# Sheet2.net
KiCad netlist of a schematic drawn in Altium Designer
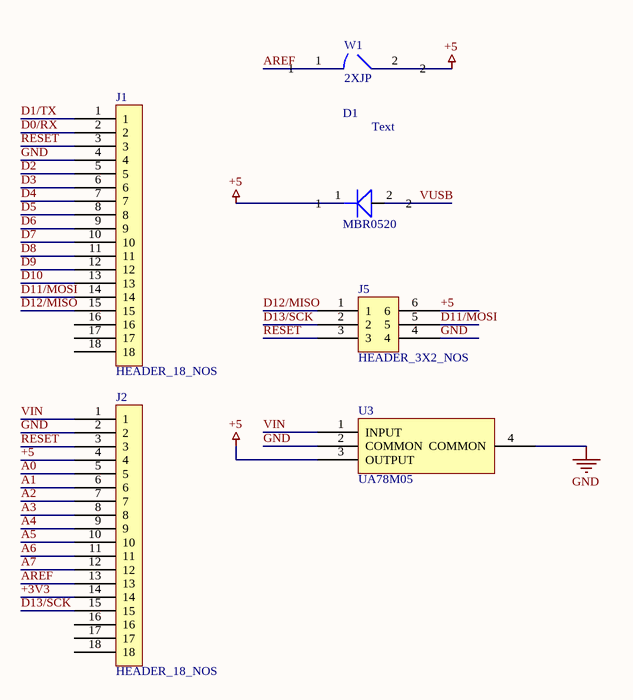
[diagram p0: Sheet2.SchDoc]

(export (version "E")
  (design (tool "Eeschema 10.0.6"))
  (components
    (comp (ref "D1")
      (value "MBR0520")
      (footprint "shotkey diode sod962")
      (libsource (lib "diode") (part "Component_1"))
    )
    (comp (ref "J1")
      (value "HEADER_18_NOS")
      (footprint "DIP18")
      (libsource (lib "18_x_1_header_pins") (part "Component_1"))
    )
    (comp (ref "J2")
      (value "HEADER_18_NOS")
      (footprint "DIP18")
      (libsource (lib "18_x_1_header_pins") (part "Component_1"))
    )
    (comp (ref "J5")
      (value "HEADER_3X2_NOS")
      (footprint "DIP6")
      (libsource (lib "3x2_header") (part "Component_1"))
    )
    (comp (ref "U3")
      (value "UA78M05")
      (footprint "SOT223-4")
      (libsource (lib "vol_reg") (part "Component_1"))
    )
    (comp (ref "W1") (value "2XJP") (footprint "switch") (libsource (lib "switch") (part "Component_1")))
  )
  (nets
    (net (code "1") (name "+5") (class "Default")
      (node (ref "D1") (pin "1") (pinfunction "1_1") (pintype "passive"))
      (node (ref "J2") (pin "4") (pinfunction "4_4") (pintype "passive"))
      (node (ref "J5") (pin "6") (pinfunction "6_6") (pintype "passive"))
      (node (ref "U3") (pin "3") (pinfunction "OUTPUT_3") (pintype "passive"))
      (node (ref "W1") (pin "2") (pinfunction "2_2") (pintype "passive"))
    )
    (net (code "2") (name "/+3V3") (class "Default")
      (node (ref "J2") (pin "14") (pinfunction "14_14") (pintype "passive"))
    )
    (net (code "3") (name "/A0") (class "Default")
      (node (ref "J2") (pin "5") (pinfunction "5_5") (pintype "passive"))
    )
    (net (code "4") (name "/A1") (class "Default")
      (node (ref "J2") (pin "6") (pinfunction "6_6") (pintype "passive"))
    )
    (net (code "5") (name "/A2") (class "Default")
      (node (ref "J2") (pin "7") (pinfunction "7_7") (pintype "passive"))
    )
    (net (code "6") (name "/A3") (class "Default")
      (node (ref "J2") (pin "8") (pinfunction "8_8") (pintype "passive"))
    )
    (net (code "7") (name "/A4") (class "Default")
      (node (ref "J2") (pin "9") (pinfunction "9_9") (pintype "passive"))
    )
    (net (code "8") (name "/A5") (class "Default")
      (node (ref "J2") (pin "10") (pinfunction "10_10") (pintype "passive"))
    )
    (net (code "9") (name "/A6") (class "Default")
      (node (ref "J2") (pin "11") (pinfunction "11_11") (pintype "passive"))
    )
    (net (code "10") (name "/A7") (class "Default")
      (node (ref "J2") (pin "12") (pinfunction "12_12") (pintype "passive"))
    )
    (net (code "11") (name "/AREF") (class "Default")
      (node (ref "J2") (pin "13") (pinfunction "13_13") (pintype "passive"))
      (node (ref "W1") (pin "1") (pinfunction "1_1") (pintype "passive"))
    )
    (net (code "12") (name "/D0{slash}RX") (class "Default")
      (node (ref "J1") (pin "2") (pinfunction "2_2") (pintype "passive"))
    )
    (net (code "13") (name "/D1{slash}TX") (class "Default")
      (node (ref "J1") (pin "1") (pinfunction "1_1") (pintype "passive"))
    )
    (net (code "14") (name "/D2") (class "Default")
      (node (ref "J1") (pin "5") (pinfunction "5_5") (pintype "passive"))
    )
    (net (code "15") (name "/D3") (class "Default")
      (node (ref "J1") (pin "6") (pinfunction "6_6") (pintype "passive"))
    )
    (net (code "16") (name "/D4") (class "Default")
      (node (ref "J1") (pin "7") (pinfunction "7_7") (pintype "passive"))
    )
    (net (code "17") (name "/D5") (class "Default")
      (node (ref "J1") (pin "8") (pinfunction "8_8") (pintype "passive"))
    )
    (net (code "18") (name "/D6") (class "Default")
      (node (ref "J1") (pin "9") (pinfunction "9_9") (pintype "passive"))
    )
    (net (code "19") (name "/D7") (class "Default")
      (node (ref "J1") (pin "10") (pinfunction "10_10") (pintype "passive"))
    )
    (net (code "20") (name "/D8") (class "Default")
      (node (ref "J1") (pin "11") (pinfunction "11_11") (pintype "passive"))
    )
    (net (code "21") (name "/D9") (class "Default")
      (node (ref "J1") (pin "12") (pinfunction "12_12") (pintype "passive"))
    )
    (net (code "22") (name "/D10") (class "Default")
      (node (ref "J1") (pin "13") (pinfunction "13_13") (pintype "passive"))
    )
    (net (code "23") (name "/D11{slash}MOSI") (class "Default")
      (node (ref "J1") (pin "14") (pinfunction "14_14") (pintype "passive"))
      (node (ref "J5") (pin "5") (pinfunction "5_5") (pintype "passive"))
    )
    (net (code "24") (name "/D12{slash}MISO") (class "Default")
      (node (ref "J1") (pin "15") (pinfunction "15_15") (pintype "passive"))
      (node (ref "J5") (pin "1") (pinfunction "1_1") (pintype "passive"))
    )
    (net (code "25") (name "/D13{slash}SCK") (class "Default")
      (node (ref "J2") (pin "15") (pinfunction "15_15") (pintype "passive"))
      (node (ref "J5") (pin "2") (pinfunction "2_2") (pintype "passive"))
    )
    (net (code "26") (name "/RESET") (class "Default")
      (node (ref "J1") (pin "3") (pinfunction "3_3") (pintype "passive"))
      (node (ref "J2") (pin "3") (pinfunction "3_3") (pintype "passive"))
      (node (ref "J5") (pin "3") (pinfunction "3_3") (pintype "passive"))
    )
    (net (code "27") (name "/VIN") (class "Default")
      (node (ref "J2") (pin "1") (pinfunction "1_1") (pintype "passive"))
      (node (ref "U3") (pin "1") (pinfunction "INPUT_1") (pintype "passive"))
    )
    (net (code "28") (name "/VUSB") (class "Default")
      (node (ref "D1") (pin "2") (pinfunction "2_2") (pintype "passive"))
    )
    (net (code "29") (name "GND") (class "Default")
      (node (ref "J1") (pin "4") (pinfunction "4_4") (pintype "passive"))
      (node (ref "J2") (pin "2") (pinfunction "2_2") (pintype "passive"))
      (node (ref "J5") (pin "4") (pinfunction "4_4") (pintype "passive"))
      (node (ref "U3") (pin "2") (pinfunction "COMMON_2") (pintype "passive"))
      (node (ref "U3") (pin "4") (pinfunction "COMMON_4") (pintype "passive"))
    )
    (net (code "30") (name "unconnected-(J1-Pad16)") (class "Default")
      (node (ref "J1") (pin "16") (pinfunction "16_16") (pintype "passive"))
    )
    (net (code "31") (name "unconnected-(J1-Pad17)") (class "Default")
      (node (ref "J1") (pin "17") (pinfunction "17_17") (pintype "passive"))
    )
    (net (code "32") (name "unconnected-(J1-Pad18)") (class "Default")
      (node (ref "J1") (pin "18") (pinfunction "18_18") (pintype "passive"))
    )
    (net (code "33") (name "unconnected-(J2-Pad16)") (class "Default")
      (node (ref "J2") (pin "16") (pinfunction "16_16") (pintype "passive"))
    )
    (net (code "34") (name "unconnected-(J2-Pad17)") (class "Default")
      (node (ref "J2") (pin "17") (pinfunction "17_17") (pintype "passive"))
    )
    (net (code "35") (name "unconnected-(J2-Pad18)") (class "Default")
      (node (ref "J2") (pin "18") (pinfunction "18_18") (pintype "passive"))
    )
  )
)
